# Shield_V1_0.net
KiCad netlist of a schematic drawn in EAGLE
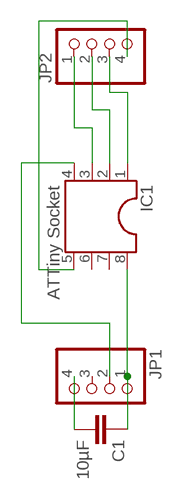
[diagram p0: schematic, sheet 1]

(export (version "E")
  (design (tool "Eeschema 10.0.6"))
  (components
    (comp (ref "C1")
      (value "10µF")
      (footprint "eagle-import:C2.5-3")
      (libsource (lib "eagle-import") (part "C2,5-3"))
    )
    (comp (ref "IC1")
      (value "ATTiny Socket")
      (footprint "eagle-import:SOCKET-08")
      (libsource (lib "eagle-import") (part "DIL8S"))
    )
    (comp (ref "JP1")
      (value "PINHD-1X4")
      (footprint "eagle-import:1X04")
      (libsource (lib "eagle-import") (part "PINHD-1X4"))
    )
    (comp (ref "JP2")
      (value "PINHD-1X4")
      (footprint "eagle-import:1X04")
      (libsource (lib "eagle-import") (part "PINHD-1X4"))
    )
  )
  (nets
    (net (code "1") (name "Net-(C1-Pad1)") (class "Default")
      (node (ref "C1") (pin "1") (pinfunction "1_1") (pintype "passive"))
      (node (ref "IC1") (pin "8") (pinfunction "8_8") (pintype "passive"))
      (node (ref "JP1") (pin "1") (pinfunction "1_1") (pintype "passive"))
    )
    (net (code "2") (name "Net-(C1-Pad2)") (class "Default")
      (node (ref "C1") (pin "2") (pinfunction "2_2") (pintype "passive"))
      (node (ref "JP1") (pin "4") (pinfunction "4_4") (pintype "passive"))
    )
    (net (code "3") (name "Net-(IC1-Pad1)") (class "Default")
      (node (ref "IC1") (pin "1") (pinfunction "1_1") (pintype "passive"))
      (node (ref "JP2") (pin "3") (pinfunction "3_3") (pintype "passive"))
    )
    (net (code "4") (name "Net-(IC1-Pad2)") (class "Default")
      (node (ref "IC1") (pin "2") (pinfunction "2_2") (pintype "passive"))
      (node (ref "JP2") (pin "2") (pinfunction "2_2") (pintype "passive"))
    )
    (net (code "5") (name "Net-(IC1-Pad3)") (class "Default")
      (node (ref "IC1") (pin "3") (pinfunction "3_3") (pintype "passive"))
      (node (ref "JP2") (pin "1") (pinfunction "1_1") (pintype "passive"))
    )
    (net (code "6") (name "Net-(IC1-Pad4)") (class "Default")
      (node (ref "IC1") (pin "4") (pinfunction "4_4") (pintype "passive"))
      (node (ref "JP1") (pin "2") (pinfunction "2_2") (pintype "passive"))
    )
    (net (code "7") (name "Net-(IC1-Pad5)") (class "Default")
      (node (ref "IC1") (pin "5") (pinfunction "5_5") (pintype "passive"))
      (node (ref "JP2") (pin "4") (pinfunction "4_4") (pintype "passive"))
    )
    (net (code "8") (name "unconnected-(IC1-Pad6)") (class "Default")
      (node (ref "IC1") (pin "6") (pinfunction "6_6") (pintype "passive"))
    )
    (net (code "9") (name "unconnected-(IC1-Pad7)") (class "Default")
      (node (ref "IC1") (pin "7") (pinfunction "7_7") (pintype "passive"))
    )
    (net (code "10") (name "unconnected-(JP1-Pad3)") (class "Default")
      (node (ref "JP1") (pin "3") (pinfunction "3_3") (pintype "passive"))
    )
  )
)
